# Ethernet_v1.net
KiCad netlist of a schematic drawn in EAGLE
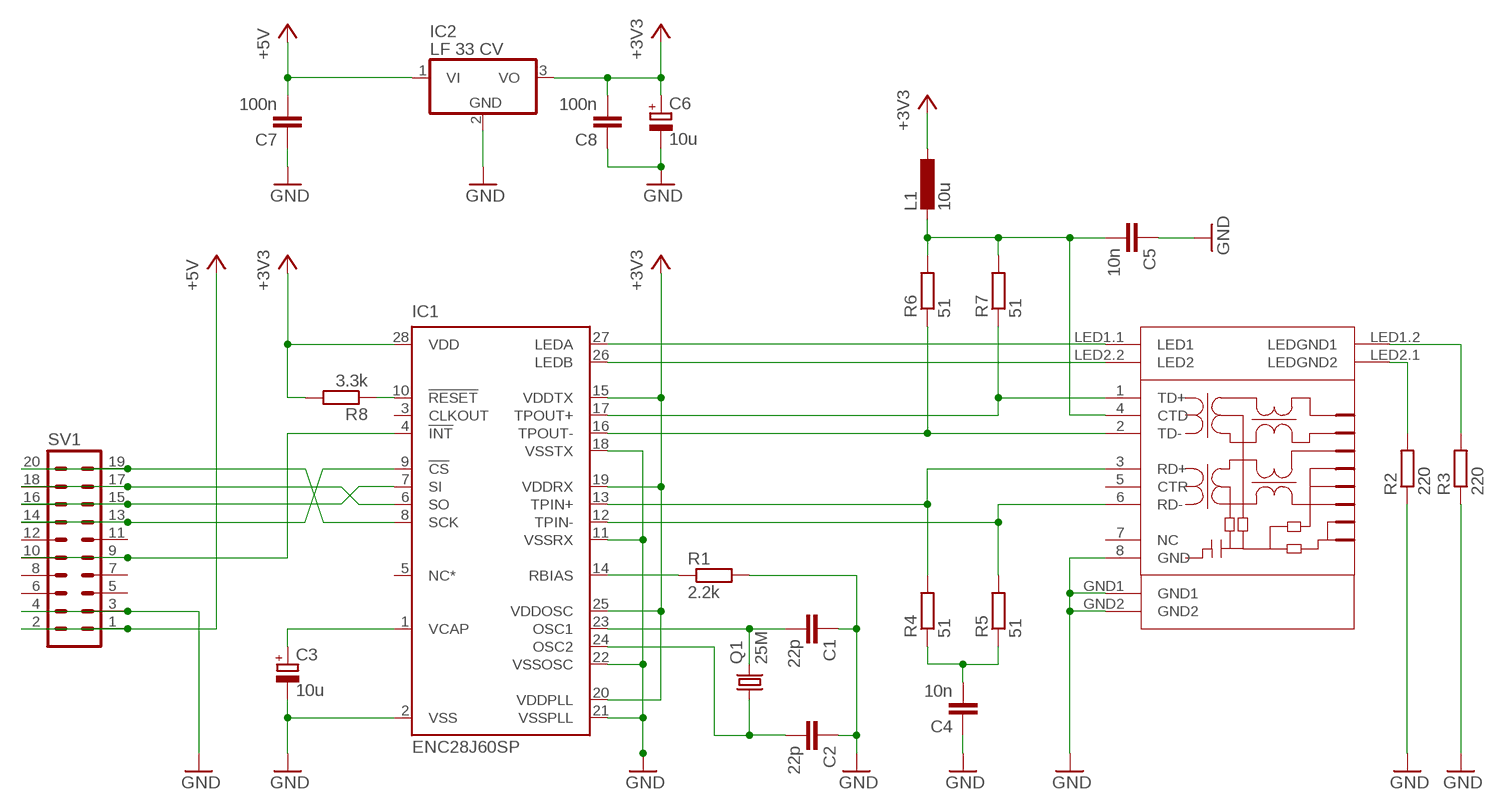
[diagram p0: schematic, sheet 1]

(export (version "E")
  (design (tool "Eeschema 10.0.6"))
  (components
    (comp (ref "C1")
      (value "22p")
      (footprint "eagle-import:C025-024X044")
      (libsource (lib "eagle-import") (part "C-EU025-024X044"))
    )
    (comp (ref "C2")
      (value "22p")
      (footprint "eagle-import:C025-024X044")
      (libsource (lib "eagle-import") (part "C-EU025-024X044"))
    )
    (comp (ref "C3")
      (value "10u")
      (footprint "eagle-import:E2-5")
      (libsource (lib "eagle-import") (part "CPOL-EUE2-5"))
    )
    (comp (ref "C4")
      (value "10n")
      (footprint "eagle-import:C025-025X050")
      (libsource (lib "eagle-import") (part "C-EU025-025X050"))
    )
    (comp (ref "C5")
      (value "10n")
      (footprint "eagle-import:C025-025X050")
      (libsource (lib "eagle-import") (part "C-EU025-025X050"))
    )
    (comp (ref "C6")
      (value "10u")
      (footprint "eagle-import:E2-5")
      (libsource (lib "eagle-import") (part "CPOL-EUE2-5"))
    )
    (comp (ref "C7")
      (value "100n")
      (footprint "eagle-import:C025-025X050")
      (libsource (lib "eagle-import") (part "C-EU025-025X050"))
    )
    (comp (ref "C8")
      (value "100n")
      (footprint "eagle-import:C025-025X050")
      (libsource (lib "eagle-import") (part "C-EU025-025X050"))
    )
    (comp (ref "IC1")
      (value "ENC28J60SP")
      (footprint "eagle-import:DIL28-3")
      (fields (field (name "MF") "MICROCHIP") (field (name "MPN") "ENC28J60/SP"))
      (libsource (lib "eagle-import") (part "ENC28J60SP"))
    )
    (comp (ref "IC2")
      (value "LF 33 CV")
      (footprint "eagle-import:TO220V")
      (libsource (lib "eagle-import") (part "78TV8"))
    )
    (comp (ref "L1")
      (value "10u")
      (footprint "eagle-import:0207_10")
      (libsource (lib "eagle-import") (part "L-EU0207/10"))
    )
    (comp (ref "Q1")
      (value "25M")
      (footprint "eagle-import:HC49U-V")
      (libsource (lib "eagle-import") (part "CRYSTALHC49U-V"))
    )
    (comp (ref "R1")
      (value "2.2k")
      (footprint "eagle-import:0207_2V")
      (libsource (lib "eagle-import") (part "R-EU_0207/2V"))
    )
    (comp (ref "R2")
      (value "220")
      (footprint "eagle-import:0207_2V")
      (libsource (lib "eagle-import") (part "R-EU_0207/2V"))
    )
    (comp (ref "R3")
      (value "220")
      (footprint "eagle-import:0207_2V")
      (libsource (lib "eagle-import") (part "R-EU_0207/2V"))
    )
    (comp (ref "R4")
      (value "51")
      (footprint "eagle-import:0207_2V")
      (libsource (lib "eagle-import") (part "R-EU_0207/2V"))
    )
    (comp (ref "R5")
      (value "51")
      (footprint "eagle-import:0207_2V")
      (libsource (lib "eagle-import") (part "R-EU_0207/2V"))
    )
    (comp (ref "R6")
      (value "51")
      (footprint "eagle-import:0207_2V")
      (libsource (lib "eagle-import") (part "R-EU_0207/2V"))
    )
    (comp (ref "R7")
      (value "51")
      (footprint "eagle-import:0207_2V")
      (libsource (lib "eagle-import") (part "R-EU_0207/2V"))
    )
    (comp (ref "R8")
      (value "3.3k")
      (footprint "eagle-import:0207_2V")
      (libsource (lib "eagle-import") (part "R-EU_0207/2V"))
    )
    (comp (ref "SV1")
      (value "MA10-2W")
      (footprint "eagle-import:MA10-2W")
      (libsource (lib "eagle-import") (part "MA10-2W"))
    )
    (comp (ref "U$1")
      (value "TRJ0011")
      (footprint "eagle-import:TRJ0011")
      (libsource (lib "eagle-import") (part "TRJ0011"))
    )
  )
  (nets
    (net (code "1") (name "+3V3") (class "Default")
      (node (ref "C6") (pin "+") (pinfunction "+_+") (pintype "passive"))
      (node (ref "C8") (pin "2") (pinfunction "2_2") (pintype "passive"))
      (node (ref "IC1") (pin "15") (pinfunction "VDDTX_15") (pintype "input"))
      (node (ref "IC1") (pin "19") (pinfunction "VDDRX_19") (pintype "input"))
      (node (ref "IC1") (pin "20") (pinfunction "VDDPLL_20") (pintype "input"))
      (node (ref "IC1") (pin "25") (pinfunction "VDDOSC_25") (pintype "input"))
      (node (ref "IC1") (pin "28") (pinfunction "VDD_28") (pintype "input"))
      (node (ref "IC2") (pin "3") (pinfunction "VO_3") (pintype "passive"))
      (node (ref "L1") (pin "1") (pinfunction "1_1") (pintype "passive"))
      (node (ref "R8") (pin "2") (pinfunction "2_2") (pintype "passive"))
    )
    (net (code "2") (name "+5V") (class "Default")
      (node (ref "C7") (pin "2") (pinfunction "2_2") (pintype "passive"))
      (node (ref "IC2") (pin "1") (pinfunction "VI_1") (pintype "input"))
      (node (ref "SV1") (pin "1") (pinfunction "1_1") (pintype "passive"))
      (node (ref "SV1") (pin "2") (pinfunction "2_2") (pintype "passive"))
    )
    (net (code "3") (name "GND") (class "Default")
      (node (ref "C1") (pin "1") (pinfunction "1_1") (pintype "passive"))
      (node (ref "C2") (pin "1") (pinfunction "1_1") (pintype "passive"))
      (node (ref "C3") (pin "-") (pinfunction "-_-") (pintype "passive"))
      (node (ref "C4") (pin "1") (pinfunction "1_1") (pintype "passive"))
      (node (ref "C5") (pin "1") (pinfunction "1_1") (pintype "passive"))
      (node (ref "C6") (pin "-") (pinfunction "-_-") (pintype "passive"))
      (node (ref "C7") (pin "1") (pinfunction "1_1") (pintype "passive"))
      (node (ref "C8") (pin "1") (pinfunction "1_1") (pintype "passive"))
      (node (ref "IC1") (pin "11") (pinfunction "VSSRX_11") (pintype "input"))
      (node (ref "IC1") (pin "18") (pinfunction "VSSTX_18") (pintype "input"))
      (node (ref "IC1") (pin "2") (pinfunction "VSS_2") (pintype "input"))
      (node (ref "IC1") (pin "21") (pinfunction "VSSPLL_21") (pintype "input"))
      (node (ref "IC1") (pin "22") (pinfunction "VSSOSC_22") (pintype "input"))
      (node (ref "IC2") (pin "2") (pinfunction "GND_2") (pintype "passive"))
      (node (ref "R1") (pin "2") (pinfunction "2_2") (pintype "passive"))
      (node (ref "R2") (pin "1") (pinfunction "1_1") (pintype "passive"))
      (node (ref "R3") (pin "1") (pinfunction "1_1") (pintype "passive"))
      (node (ref "SV1") (pin "3") (pinfunction "3_3") (pintype "passive"))
      (node (ref "SV1") (pin "4") (pinfunction "4_4") (pintype "passive"))
      (node (ref "U$1") (pin "8") (pinfunction "GND_8") (pintype "bidirectional"))
      (node (ref "U$1") (pin "GND1") (pinfunction "GND1_GND1") (pintype "bidirectional"))
      (node (ref "U$1") (pin "GND2") (pinfunction "GND2_GND2") (pintype "bidirectional"))
    )
    (net (code "4") (name "Net-(C4-Pad2)") (class "Default")
      (node (ref "C4") (pin "2") (pinfunction "2_2") (pintype "passive"))
      (node (ref "R4") (pin "1") (pinfunction "1_1") (pintype "passive"))
      (node (ref "R5") (pin "1") (pinfunction "1_1") (pintype "passive"))
    )
    (net (code "5") (name "Net-(IC1-LEDA)") (class "Default")
      (node (ref "IC1") (pin "27") (pinfunction "LEDA_27") (pintype "output"))
      (node (ref "U$1") (pin "LED1.1") (pinfunction "LED1_LED1.1") (pintype "bidirectional"))
    )
    (net (code "6") (name "Net-(IC1-LEDB)") (class "Default")
      (node (ref "IC1") (pin "26") (pinfunction "LEDB_26") (pintype "output"))
      (node (ref "U$1") (pin "LED2.2") (pinfunction "LED2_LED2.2") (pintype "bidirectional"))
    )
    (net (code "7") (name "Net-(IC1-OSC1)") (class "Default")
      (node (ref "C1") (pin "2") (pinfunction "2_2") (pintype "passive"))
      (node (ref "IC1") (pin "23") (pinfunction "OSC1_23") (pintype "input"))
      (node (ref "Q1") (pin "2") (pinfunction "2_2") (pintype "passive"))
    )
    (net (code "8") (name "Net-(IC1-OSC2)") (class "Default")
      (node (ref "C2") (pin "2") (pinfunction "2_2") (pintype "passive"))
      (node (ref "IC1") (pin "24") (pinfunction "OSC2_24") (pintype "output"))
      (node (ref "Q1") (pin "1") (pinfunction "1_1") (pintype "passive"))
    )
    (net (code "9") (name "Net-(IC1-RBIAS)") (class "Default")
      (node (ref "IC1") (pin "14") (pinfunction "RBIAS_14") (pintype "input"))
      (node (ref "R1") (pin "1") (pinfunction "1_1") (pintype "passive"))
    )
    (net (code "10") (name "Net-(IC1-SCK)") (class "Default")
      (node (ref "IC1") (pin "8") (pinfunction "SCK_8") (pintype "input"))
      (node (ref "SV1") (pin "19") (pinfunction "19_19") (pintype "passive"))
      (node (ref "SV1") (pin "20") (pinfunction "20_20") (pintype "passive"))
    )
    (net (code "11") (name "Net-(IC1-SI)") (class "Default")
      (node (ref "IC1") (pin "7") (pinfunction "SI_7") (pintype "input"))
      (node (ref "SV1") (pin "15") (pinfunction "15_15") (pintype "passive"))
      (node (ref "SV1") (pin "16") (pinfunction "16_16") (pintype "passive"))
    )
    (net (code "12") (name "Net-(IC1-SO)") (class "Default")
      (node (ref "IC1") (pin "6") (pinfunction "SO_6") (pintype "output"))
      (node (ref "SV1") (pin "17") (pinfunction "17_17") (pintype "passive"))
      (node (ref "SV1") (pin "18") (pinfunction "18_18") (pintype "passive"))
    )
    (net (code "13") (name "Net-(IC1-TPIN+)") (class "Default")
      (node (ref "IC1") (pin "13") (pinfunction "TPIN+_13") (pintype "input"))
      (node (ref "R4") (pin "2") (pinfunction "2_2") (pintype "passive"))
      (node (ref "U$1") (pin "3") (pinfunction "RD+_3") (pintype "bidirectional"))
    )
    (net (code "14") (name "Net-(IC1-TPIN-)") (class "Default")
      (node (ref "IC1") (pin "12") (pinfunction "TPIN-_12") (pintype "input"))
      (node (ref "R5") (pin "2") (pinfunction "2_2") (pintype "passive"))
      (node (ref "U$1") (pin "6") (pinfunction "RD-_6") (pintype "bidirectional"))
    )
    (net (code "15") (name "Net-(IC1-TPOUT+)") (class "Default")
      (node (ref "IC1") (pin "17") (pinfunction "TPOUT+_17") (pintype "output"))
      (node (ref "R7") (pin "1") (pinfunction "1_1") (pintype "passive"))
      (node (ref "U$1") (pin "1") (pinfunction "TD+_1") (pintype "bidirectional"))
    )
    (net (code "16") (name "Net-(IC1-TPOUT-)") (class "Default")
      (node (ref "IC1") (pin "16") (pinfunction "TPOUT-_16") (pintype "output"))
      (node (ref "R6") (pin "1") (pinfunction "1_1") (pintype "passive"))
      (node (ref "U$1") (pin "2") (pinfunction "TD-_2") (pintype "bidirectional"))
    )
    (net (code "17") (name "Net-(IC1-VCAP)") (class "Default")
      (node (ref "C3") (pin "+") (pinfunction "+_+") (pintype "passive"))
      (node (ref "IC1") (pin "1") (pinfunction "VCAP_1") (pintype "input"))
    )
    (net (code "18") (name "Net-(IC1-~{CS})") (class "Default")
      (node (ref "IC1") (pin "9") (pinfunction "~{CS}_9") (pintype "input"))
      (node (ref "SV1") (pin "13") (pinfunction "13_13") (pintype "passive"))
      (node (ref "SV1") (pin "14") (pinfunction "14_14") (pintype "passive"))
    )
    (net (code "19") (name "Net-(IC1-~{INT})") (class "Default")
      (node (ref "IC1") (pin "4") (pinfunction "~{INT}_4") (pintype "output"))
      (node (ref "SV1") (pin "10") (pinfunction "10_10") (pintype "passive"))
      (node (ref "SV1") (pin "9") (pinfunction "9_9") (pintype "passive"))
    )
    (net (code "20") (name "Net-(IC1-~{RESET})") (class "Default")
      (node (ref "IC1") (pin "10") (pinfunction "~{RESET}_10") (pintype "input"))
      (node (ref "R8") (pin "1") (pinfunction "1_1") (pintype "passive"))
    )
    (net (code "21") (name "Net-(U$1-CTD)") (class "Default")
      (node (ref "C5") (pin "2") (pinfunction "2_2") (pintype "passive"))
      (node (ref "L1") (pin "2") (pinfunction "2_2") (pintype "passive"))
      (node (ref "R6") (pin "2") (pinfunction "2_2") (pintype "passive"))
      (node (ref "R7") (pin "2") (pinfunction "2_2") (pintype "passive"))
      (node (ref "U$1") (pin "4") (pinfunction "CTD_4") (pintype "bidirectional"))
    )
    (net (code "22") (name "Net-(U$1-LEDGND1)") (class "Default")
      (node (ref "R3") (pin "2") (pinfunction "2_2") (pintype "passive"))
      (node (ref "U$1") (pin "LED1.2") (pinfunction "LEDGND1_LED1.2") (pintype "bidirectional"))
    )
    (net (code "23") (name "Net-(U$1-LEDGND2)") (class "Default")
      (node (ref "R2") (pin "2") (pinfunction "2_2") (pintype "passive"))
      (node (ref "U$1") (pin "LED2.1") (pinfunction "LEDGND2_LED2.1") (pintype "bidirectional"))
    )
    (net (code "24") (name "unconnected-(IC1-CLKOUT-Pad3)") (class "Default")
      (node (ref "IC1") (pin "3") (pinfunction "CLKOUT_3") (pintype "output"))
    )
    (net (code "25") (name "unconnected-(IC1-NC*-Pad5)") (class "Default")
      (node (ref "IC1") (pin "5") (pinfunction "NC*_5") (pintype "output"))
    )
    (net (code "26") (name "unconnected-(SV1-Pad5)") (class "Default")
      (node (ref "SV1") (pin "5") (pinfunction "5_5") (pintype "passive"))
    )
    (net (code "27") (name "unconnected-(SV1-Pad6)") (class "Default")
      (node (ref "SV1") (pin "6") (pinfunction "6_6") (pintype "passive"))
    )
    (net (code "28") (name "unconnected-(SV1-Pad7)") (class "Default")
      (node (ref "SV1") (pin "7") (pinfunction "7_7") (pintype "passive"))
    )
    (net (code "29") (name "unconnected-(SV1-Pad8)") (class "Default")
      (node (ref "SV1") (pin "8") (pinfunction "8_8") (pintype "passive"))
    )
    (net (code "30") (name "unconnected-(SV1-Pad11)") (class "Default")
      (node (ref "SV1") (pin "11") (pinfunction "11_11") (pintype "passive"))
    )
    (net (code "31") (name "unconnected-(SV1-Pad12)") (class "Default")
      (node (ref "SV1") (pin "12") (pinfunction "12_12") (pintype "passive"))
    )
    (net (code "32") (name "unconnected-(U$1-CTR-Pad5)") (class "Default")
      (node (ref "U$1") (pin "5") (pinfunction "CTR_5") (pintype "bidirectional"))
    )
    (net (code "33") (name "unconnected-(U$1-NC-Pad7)") (class "Default")
      (node (ref "U$1") (pin "7") (pinfunction "NC_7") (pintype "bidirectional"))
    )
  )
)
